# Fluorometer.net
KiCad netlist of a schematic drawn in EAGLE
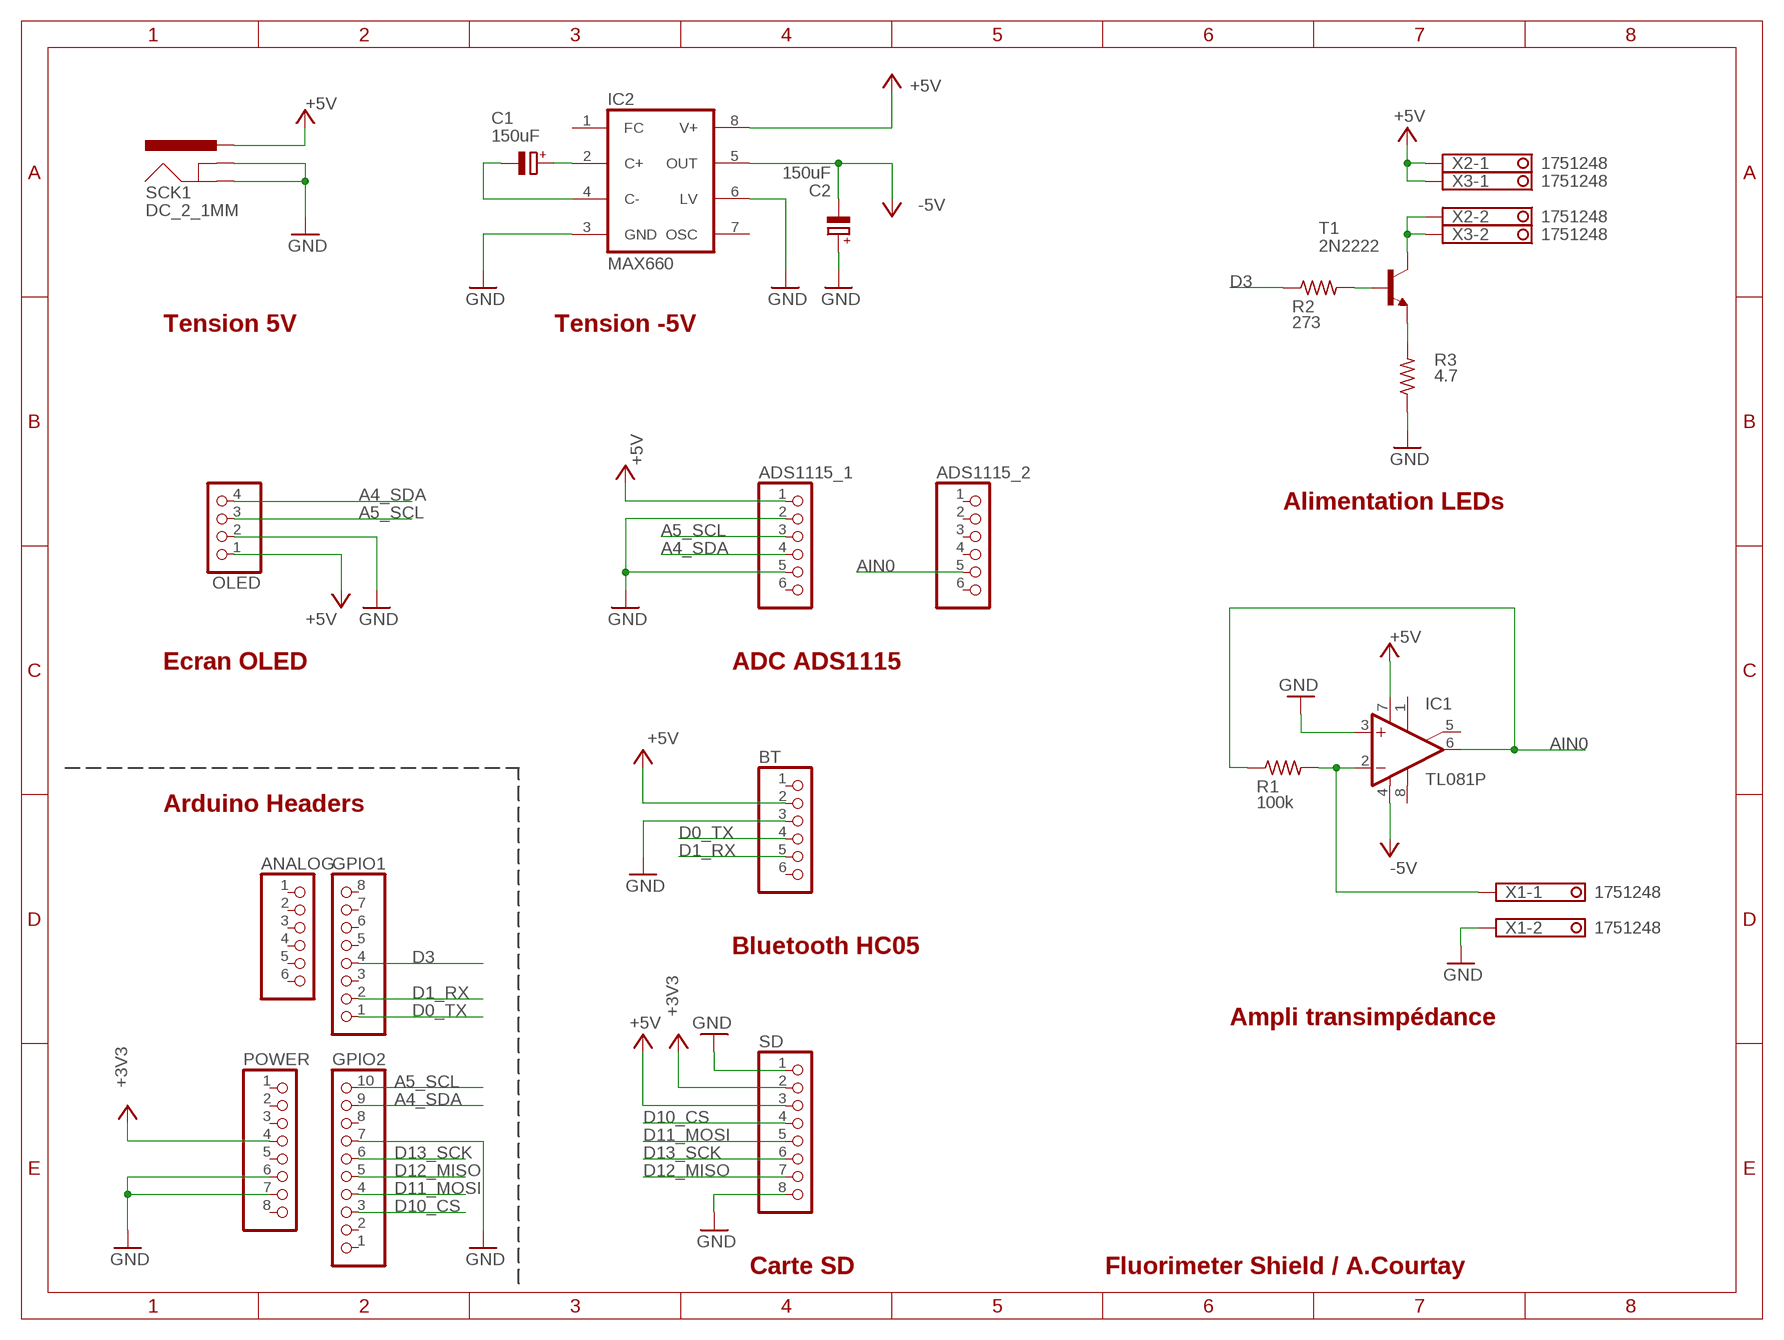
[diagram p0: schematic, sheet 1]

(export (version "E")
  (design (tool "Eeschema 10.0.6"))
  (components
    (comp (ref "ADS1115_1")
      (value "PINHD-1X6")
      (footprint "eagle-import:1X06")
      (libsource (lib "eagle-import") (part "pinhead_325_PINHD-1X6"))
    )
    (comp (ref "ADS1115_2")
      (value "PINHD-1X6")
      (footprint "eagle-import:1X06")
      (libsource (lib "eagle-import") (part "pinhead_325_PINHD-1X6"))
    )
    (comp (ref "ANALOG")
      (value "PINHD-1X6")
      (footprint "eagle-import:1X06")
      (libsource (lib "eagle-import") (part "PINHD-1X6"))
    )
    (comp (ref "BT")
      (value "PINHD-1X6")
      (footprint "eagle-import:1X06")
      (libsource (lib "eagle-import") (part "pinhead_325_PINHD-1X6"))
    )
    (comp (ref "C1")
      (value "150uF")
      (footprint "eagle-import:E2,5-7")
      (libsource (lib "eagle-import") (part "CPOL-EUE2.5-7"))
    )
    (comp (ref "C2")
      (value "150uF")
      (footprint "eagle-import:E2,5-7")
      (libsource (lib "eagle-import") (part "CPOL-EUE2.5-7"))
    )
    (comp (ref "GPIO1")
      (value "PINHD-1X8")
      (footprint "eagle-import:1X08")
      (libsource (lib "eagle-import") (part "PINHD-1X8"))
    )
    (comp (ref "GPIO2")
      (value "PINHD-1X10")
      (footprint "eagle-import:1X10")
      (libsource (lib "eagle-import") (part "PINHD-1X10"))
    )
    (comp (ref "IC1")
      (value "TL081P")
      (footprint "eagle-import:DIL08")
      (libsource (lib "eagle-import") (part "TL081P"))
    )
    (comp (ref "IC2")
      (value "MAX660")
      (footprint "eagle-import:DIL08")
      (fields (field (name "MF") "MAXIM") (field (name "MPN") "MAX660CPA"))
      (libsource (lib "eagle-import") (part "MAX660CPA"))
    )
    (comp (ref "OLED")
      (value "PINHD-1X4")
      (footprint "eagle-import:1X04")
      (libsource (lib "eagle-import") (part "PINHD-1X4"))
    )
    (comp (ref "POWER")
      (value "PINHD-1X8")
      (footprint "eagle-import:1X08")
      (libsource (lib "eagle-import") (part "PINHD-1X8"))
    )
    (comp (ref "R1")
      (value "100k")
      (footprint "eagle-import:0204_7")
      (libsource (lib "eagle-import") (part "R-US_0204/7"))
    )
    (comp (ref "R2")
      (value "273")
      (footprint "eagle-import:0204_7")
      (libsource (lib "eagle-import") (part "R-US_0204/7"))
    )
    (comp (ref "R3")
      (value "4.7")
      (footprint "eagle-import:0204_7")
      (libsource (lib "eagle-import") (part "R-US_0204/7"))
    )
    (comp (ref "SCK1")
      (value "DC_2_1MM")
      (footprint "eagle-import:POWER_JACK_PTH")
      (libsource (lib "eagle-import") (part "POWER_JACKPTH"))
    )
    (comp (ref "SD")
      (value "PINHD-1X8")
      (footprint "eagle-import:1X08")
      (libsource (lib "eagle-import") (part "pinhead_325_PINHD-1X8"))
    )
    (comp (ref "T1")
      (value "2N2222")
      (footprint "eagle-import:TO18")
      (libsource (lib "eagle-import") (part "2N2222"))
    )
    (comp (ref "X1")
      (value "1751248")
      (footprint "eagle-import:1751248")
      (libsource (lib "eagle-import") (part "1751248"))
    )
    (comp (ref "X2")
      (value "1751248")
      (footprint "eagle-import:1751248")
      (libsource (lib "eagle-import") (part "1751248"))
    )
    (comp (ref "X3")
      (value "1751248")
      (footprint "eagle-import:1751248")
      (libsource (lib "eagle-import") (part "1751248"))
    )
  )
  (nets
    (net (code "1") (name "+3V3") (class "Default")
      (node (ref "POWER") (pin "4") (pinfunction "4_4") (pintype "passive"))
      (node (ref "SD") (pin "2") (pinfunction "2_2") (pintype "passive"))
    )
    (net (code "2") (name "+5V") (class "Default")
      (node (ref "ADS1115_1") (pin "1") (pinfunction "1_1") (pintype "passive"))
      (node (ref "BT") (pin "2") (pinfunction "2_2") (pintype "passive"))
      (node (ref "IC1") (pin "7") (pinfunction "V+_7") (pintype "power_in"))
      (node (ref "IC2") (pin "8") (pinfunction "V+_8") (pintype "power_in"))
      (node (ref "OLED") (pin "1") (pinfunction "1_1") (pintype "passive"))
      (node (ref "SCK1") (pin "PWR") (pinfunction "PWR_PWR") (pintype "bidirectional"))
      (node (ref "SD") (pin "3") (pinfunction "3_3") (pintype "passive"))
      (node (ref "X2") (pin "1") (pinfunction "K_1") (pintype "passive"))
      (node (ref "X3") (pin "1") (pinfunction "K_1") (pintype "passive"))
    )
    (net (code "3") (name "-5V") (class "Default")
      (node (ref "C2") (pin "-") (pinfunction "-_-") (pintype "passive"))
      (node (ref "IC1") (pin "4") (pinfunction "V-_4") (pintype "power_in"))
      (node (ref "IC2") (pin "5") (pinfunction "OUT_5") (pintype "power_in"))
    )
    (net (code "4") (name "/A4_SDA") (class "Default")
      (node (ref "ADS1115_1") (pin "4") (pinfunction "4_4") (pintype "passive"))
      (node (ref "GPIO2") (pin "9") (pinfunction "9_9") (pintype "passive"))
      (node (ref "OLED") (pin "4") (pinfunction "4_4") (pintype "passive"))
    )
    (net (code "5") (name "/A5_SCL") (class "Default")
      (node (ref "ADS1115_1") (pin "3") (pinfunction "3_3") (pintype "passive"))
      (node (ref "GPIO2") (pin "10") (pinfunction "10_10") (pintype "passive"))
      (node (ref "OLED") (pin "3") (pinfunction "3_3") (pintype "passive"))
    )
    (net (code "6") (name "/AIN0") (class "Default")
      (node (ref "ADS1115_2") (pin "5") (pinfunction "5_5") (pintype "passive"))
      (node (ref "IC1") (pin "6") (pinfunction "OUT_6") (pintype "output"))
      (node (ref "R1") (pin "1") (pinfunction "1_1") (pintype "passive"))
    )
    (net (code "7") (name "/D0_TX") (class "Default")
      (node (ref "BT") (pin "4") (pinfunction "4_4") (pintype "passive"))
      (node (ref "GPIO1") (pin "1") (pinfunction "1_1") (pintype "passive"))
    )
    (net (code "8") (name "/D1_RX") (class "Default")
      (node (ref "BT") (pin "5") (pinfunction "5_5") (pintype "passive"))
      (node (ref "GPIO1") (pin "2") (pinfunction "2_2") (pintype "passive"))
    )
    (net (code "9") (name "/D3") (class "Default")
      (node (ref "GPIO1") (pin "4") (pinfunction "4_4") (pintype "passive"))
      (node (ref "R2") (pin "1") (pinfunction "1_1") (pintype "passive"))
    )
    (net (code "10") (name "/D10_CS") (class "Default")
      (node (ref "GPIO2") (pin "3") (pinfunction "3_3") (pintype "passive"))
      (node (ref "SD") (pin "4") (pinfunction "4_4") (pintype "passive"))
    )
    (net (code "11") (name "/D11_MOSI") (class "Default")
      (node (ref "GPIO2") (pin "4") (pinfunction "4_4") (pintype "passive"))
      (node (ref "SD") (pin "5") (pinfunction "5_5") (pintype "passive"))
    )
    (net (code "12") (name "/D12_MISO") (class "Default")
      (node (ref "GPIO2") (pin "5") (pinfunction "5_5") (pintype "passive"))
      (node (ref "SD") (pin "7") (pinfunction "7_7") (pintype "passive"))
    )
    (net (code "13") (name "/D13_SCK") (class "Default")
      (node (ref "GPIO2") (pin "6") (pinfunction "6_6") (pintype "passive"))
      (node (ref "SD") (pin "6") (pinfunction "6_6") (pintype "passive"))
    )
    (net (code "14") (name "GND") (class "Default")
      (node (ref "ADS1115_1") (pin "2") (pinfunction "2_2") (pintype "passive"))
      (node (ref "ADS1115_1") (pin "5") (pinfunction "5_5") (pintype "passive"))
      (node (ref "BT") (pin "3") (pinfunction "3_3") (pintype "passive"))
      (node (ref "C2") (pin "+") (pinfunction "+_+") (pintype "passive"))
      (node (ref "GPIO2") (pin "7") (pinfunction "7_7") (pintype "passive"))
      (node (ref "IC1") (pin "3") (pinfunction "+IN_3") (pintype "input"))
      (node (ref "IC2") (pin "3") (pinfunction "GND_3") (pintype "power_in"))
      (node (ref "IC2") (pin "6") (pinfunction "LV_6") (pintype "passive"))
      (node (ref "OLED") (pin "2") (pinfunction "2_2") (pintype "passive"))
      (node (ref "POWER") (pin "6") (pinfunction "6_6") (pintype "passive"))
      (node (ref "POWER") (pin "7") (pinfunction "7_7") (pintype "passive"))
      (node (ref "R3") (pin "1") (pinfunction "1_1") (pintype "passive"))
      (node (ref "SCK1") (pin "GND") (pinfunction "GND_GND") (pintype "bidirectional"))
      (node (ref "SCK1") (pin "GNDBREAK") (pinfunction "GNDBREAK_GNDBREAK") (pintype "bidirectional"))
      (node (ref "SD") (pin "1") (pinfunction "1_1") (pintype "passive"))
      (node (ref "SD") (pin "8") (pinfunction "8_8") (pintype "passive"))
      (node (ref "X1") (pin "2") (pinfunction "K_2") (pintype "passive"))
    )
    (net (code "15") (name "Net-(IC1--IN)") (class "Default")
      (node (ref "IC1") (pin "2") (pinfunction "-IN_2") (pintype "input"))
      (node (ref "R1") (pin "2") (pinfunction "2_2") (pintype "passive"))
      (node (ref "X1") (pin "1") (pinfunction "K_1") (pintype "passive"))
    )
    (net (code "16") (name "Net-(IC2-C+)") (class "Default")
      (node (ref "C1") (pin "+") (pinfunction "+_+") (pintype "passive"))
      (node (ref "IC2") (pin "2") (pinfunction "C+_2") (pintype "passive"))
    )
    (net (code "17") (name "Net-(IC2-C-)") (class "Default")
      (node (ref "C1") (pin "-") (pinfunction "-_-") (pintype "passive"))
      (node (ref "IC2") (pin "4") (pinfunction "C-_4") (pintype "passive"))
    )
    (net (code "18") (name "Net-(T1-B)") (class "Default")
      (node (ref "R2") (pin "2") (pinfunction "2_2") (pintype "passive"))
      (node (ref "T1") (pin "2") (pinfunction "B_2") (pintype "passive"))
    )
    (net (code "19") (name "Net-(T1-C)") (class "Default")
      (node (ref "T1") (pin "3") (pinfunction "C_3") (pintype "passive"))
      (node (ref "X2") (pin "2") (pinfunction "K_2") (pintype "passive"))
      (node (ref "X3") (pin "2") (pinfunction "K_2") (pintype "passive"))
    )
    (net (code "20") (name "Net-(T1-E)") (class "Default")
      (node (ref "R3") (pin "2") (pinfunction "2_2") (pintype "passive"))
      (node (ref "T1") (pin "1") (pinfunction "E_1") (pintype "passive"))
    )
    (net (code "21") (name "unconnected-(ADS1115_1-Pad6)") (class "Default")
      (node (ref "ADS1115_1") (pin "6") (pinfunction "6_6") (pintype "passive"))
    )
    (net (code "22") (name "unconnected-(ADS1115_2-Pad1)") (class "Default")
      (node (ref "ADS1115_2") (pin "1") (pinfunction "1_1") (pintype "passive"))
    )
    (net (code "23") (name "unconnected-(ADS1115_2-Pad2)") (class "Default")
      (node (ref "ADS1115_2") (pin "2") (pinfunction "2_2") (pintype "passive"))
    )
    (net (code "24") (name "unconnected-(ADS1115_2-Pad3)") (class "Default")
      (node (ref "ADS1115_2") (pin "3") (pinfunction "3_3") (pintype "passive"))
    )
    (net (code "25") (name "unconnected-(ADS1115_2-Pad4)") (class "Default")
      (node (ref "ADS1115_2") (pin "4") (pinfunction "4_4") (pintype "passive"))
    )
    (net (code "26") (name "unconnected-(ADS1115_2-Pad6)") (class "Default")
      (node (ref "ADS1115_2") (pin "6") (pinfunction "6_6") (pintype "passive"))
    )
    (net (code "27") (name "unconnected-(ANALOG-Pad1)") (class "Default")
      (node (ref "ANALOG") (pin "1") (pinfunction "1_1") (pintype "passive"))
    )
    (net (code "28") (name "unconnected-(ANALOG-Pad2)") (class "Default")
      (node (ref "ANALOG") (pin "2") (pinfunction "2_2") (pintype "passive"))
    )
    (net (code "29") (name "unconnected-(ANALOG-Pad3)") (class "Default")
      (node (ref "ANALOG") (pin "3") (pinfunction "3_3") (pintype "passive"))
    )
    (net (code "30") (name "unconnected-(ANALOG-Pad4)") (class "Default")
      (node (ref "ANALOG") (pin "4") (pinfunction "4_4") (pintype "passive"))
    )
    (net (code "31") (name "unconnected-(ANALOG-Pad5)") (class "Default")
      (node (ref "ANALOG") (pin "5") (pinfunction "5_5") (pintype "passive"))
    )
    (net (code "32") (name "unconnected-(ANALOG-Pad6)") (class "Default")
      (node (ref "ANALOG") (pin "6") (pinfunction "6_6") (pintype "passive"))
    )
    (net (code "33") (name "unconnected-(BT-Pad1)") (class "Default")
      (node (ref "BT") (pin "1") (pinfunction "1_1") (pintype "passive"))
    )
    (net (code "34") (name "unconnected-(BT-Pad6)") (class "Default")
      (node (ref "BT") (pin "6") (pinfunction "6_6") (pintype "passive"))
    )
    (net (code "35") (name "unconnected-(GPIO1-Pad3)") (class "Default")
      (node (ref "GPIO1") (pin "3") (pinfunction "3_3") (pintype "passive"))
    )
    (net (code "36") (name "unconnected-(GPIO1-Pad5)") (class "Default")
      (node (ref "GPIO1") (pin "5") (pinfunction "5_5") (pintype "passive"))
    )
    (net (code "37") (name "unconnected-(GPIO1-Pad6)") (class "Default")
      (node (ref "GPIO1") (pin "6") (pinfunction "6_6") (pintype "passive"))
    )
    (net (code "38") (name "unconnected-(GPIO1-Pad7)") (class "Default")
      (node (ref "GPIO1") (pin "7") (pinfunction "7_7") (pintype "passive"))
    )
    (net (code "39") (name "unconnected-(GPIO1-Pad8)") (class "Default")
      (node (ref "GPIO1") (pin "8") (pinfunction "8_8") (pintype "passive"))
    )
    (net (code "40") (name "unconnected-(GPIO2-Pad1)") (class "Default")
      (node (ref "GPIO2") (pin "1") (pinfunction "1_1") (pintype "passive"))
    )
    (net (code "41") (name "unconnected-(GPIO2-Pad2)") (class "Default")
      (node (ref "GPIO2") (pin "2") (pinfunction "2_2") (pintype "passive"))
    )
    (net (code "42") (name "unconnected-(GPIO2-Pad8)") (class "Default")
      (node (ref "GPIO2") (pin "8") (pinfunction "8_8") (pintype "passive"))
    )
    (net (code "43") (name "unconnected-(IC1-ON1-Pad1)") (class "Default")
      (node (ref "IC1") (pin "1") (pinfunction "ON1_1") (pintype "passive"))
    )
    (net (code "44") (name "unconnected-(IC1-ON2-Pad5)") (class "Default")
      (node (ref "IC1") (pin "5") (pinfunction "ON2_5") (pintype "passive"))
    )
    (net (code "45") (name "unconnected-(IC1-OPT-Pad8)") (class "Default")
      (node (ref "IC1") (pin "8") (pinfunction "OPT_8") (pintype "passive"))
    )
    (net (code "46") (name "unconnected-(IC2-FC-Pad1)") (class "Default")
      (node (ref "IC2") (pin "1") (pinfunction "FC_1") (pintype "input"))
    )
    (net (code "47") (name "unconnected-(IC2-OSC-Pad7)") (class "Default")
      (node (ref "IC2") (pin "7") (pinfunction "OSC_7") (pintype "output"))
    )
    (net (code "48") (name "unconnected-(POWER-Pad1)") (class "Default")
      (node (ref "POWER") (pin "1") (pinfunction "1_1") (pintype "passive"))
    )
    (net (code "49") (name "unconnected-(POWER-Pad2)") (class "Default")
      (node (ref "POWER") (pin "2") (pinfunction "2_2") (pintype "passive"))
    )
    (net (code "50") (name "unconnected-(POWER-Pad3)") (class "Default")
      (node (ref "POWER") (pin "3") (pinfunction "3_3") (pintype "passive"))
    )
    (net (code "51") (name "unconnected-(POWER-Pad5)") (class "Default")
      (node (ref "POWER") (pin "5") (pinfunction "5_5") (pintype "passive"))
    )
    (net (code "52") (name "unconnected-(POWER-Pad8)") (class "Default")
      (node (ref "POWER") (pin "8") (pinfunction "8_8") (pintype "passive"))
    )
  )
)
